# analogPWM.net
KiCad netlist of a schematic drawn in Altium Designer
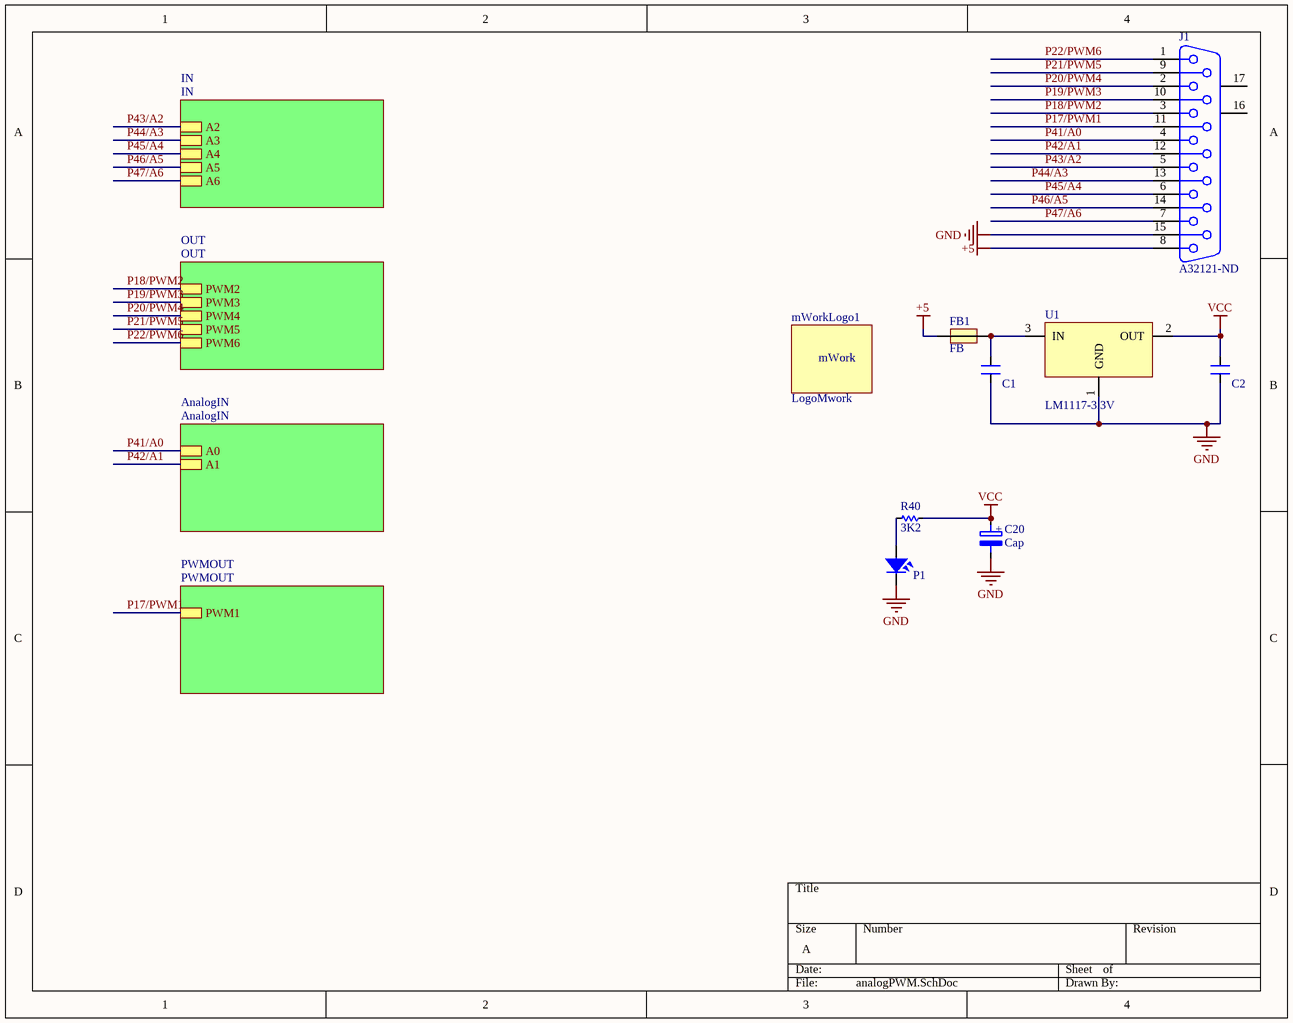
[diagram p0: analogPWM.SchDoc]

(export (version "E")
  (design (tool "Eeschema 10.0.6"))
  (components
    (comp (ref "C1") (value "100nF") (footprint "CN-SMD-0805") (libsource (lib "nhan") (part "CN")))
    (comp (ref "C2") (value "100nF") (footprint "CN-SMD-0805") (libsource (lib "nhan") (part "CN")))
    (comp (ref "C20")
      (value "Cap")
      (footprint "Cap_C")
      (description "Polarized Capacitor (Radial)")
      (libsource (lib "nhan") (part "Cap_tan"))
    )
    (comp (ref "FB1") (value "FB") (footprint "Capacitor_805") (libsource (lib "nhan") (part "FB")))
    (comp (ref "J1")
      (value "A32121-ND")
      (footprint "DB15")
      (description "Receptacle Assembly, 15 Position, Right Angle")
      (fields (field (name "PUBLISHER") "Altium Limited"))
      (libsource (lib "nhan") (part "DB15"))
    )
    (comp (ref "mWorkLogo1")
      (value "LogoMwork")
      (footprint "LogoMwork15*6")
      (libsource (lib "nhan") (part "LogoMwork"))
    )
    (comp (ref "P1")
      (value "LED")
      (footprint "LED-0805-Green")
      (libsource (lib "BanLinhKien") (part "LED SMD"))
    )
    (comp (ref "R40") (value "3K2") (footprint "RES-SMD-0805") (libsource (lib "nhan") (part "R")))
    (comp (ref "U1")
      (value "LM1117-3.3V")
      (footprint "SOT223")
      (description "800mA Low-Dropout Linear Regulator")
      (fields (field (name "CREATOR") "Nguyen Ba Bien"))
      (libsource (lib "BanLinhKien") (part "LM1117"))
    )
  )
  (nets
    (net (code "1") (name "+5") (class "Default")
      (node (ref "FB1") (pin "1") (pinfunction "1_1") (pintype "passive"))
      (node (ref "J1") (pin "8") (pinfunction "8_8") (pintype "passive"))
    )
    (net (code "2") (name "/P17{slash}PWM1") (class "Default")
      (node (ref "J1") (pin "11") (pinfunction "11_11") (pintype "passive"))
    )
    (net (code "3") (name "/P18{slash}PWM2") (class "Default")
      (node (ref "J1") (pin "3") (pinfunction "3_3") (pintype "passive"))
    )
    (net (code "4") (name "/P19{slash}PWM3") (class "Default")
      (node (ref "J1") (pin "10") (pinfunction "10_10") (pintype "passive"))
    )
    (net (code "5") (name "/P20{slash}PWM4") (class "Default")
      (node (ref "J1") (pin "2") (pinfunction "2_2") (pintype "passive"))
    )
    (net (code "6") (name "/P21{slash}PWM5") (class "Default")
      (node (ref "J1") (pin "9") (pinfunction "9_9") (pintype "passive"))
    )
    (net (code "7") (name "/P22{slash}PWM6") (class "Default")
      (node (ref "J1") (pin "1") (pinfunction "1_1") (pintype "passive"))
    )
    (net (code "8") (name "/P41{slash}A0") (class "Default")
      (node (ref "J1") (pin "4") (pinfunction "4_4") (pintype "passive"))
    )
    (net (code "9") (name "/P42{slash}A1") (class "Default")
      (node (ref "J1") (pin "12") (pinfunction "12_12") (pintype "passive"))
    )
    (net (code "10") (name "/P43{slash}A2") (class "Default")
      (node (ref "J1") (pin "5") (pinfunction "5_5") (pintype "passive"))
    )
    (net (code "11") (name "/P44{slash}A3") (class "Default")
      (node (ref "J1") (pin "13") (pinfunction "13_13") (pintype "passive"))
    )
    (net (code "12") (name "/P45{slash}A4") (class "Default")
      (node (ref "J1") (pin "6") (pinfunction "6_6") (pintype "passive"))
    )
    (net (code "13") (name "/P46{slash}A5") (class "Default")
      (node (ref "J1") (pin "14") (pinfunction "14_14") (pintype "passive"))
    )
    (net (code "14") (name "/P47{slash}A6") (class "Default")
      (node (ref "J1") (pin "7") (pinfunction "7_7") (pintype "passive"))
    )
    (net (code "15") (name "GND") (class "Default")
      (node (ref "C1") (pin "2") (pinfunction "2_2") (pintype "passive"))
      (node (ref "C2") (pin "2") (pinfunction "2_2") (pintype "passive"))
      (node (ref "C20") (pin "2") (pinfunction "2_2") (pintype "passive"))
      (node (ref "J1") (pin "15") (pinfunction "15_15") (pintype "passive"))
      (node (ref "P1") (pin "2") (pinfunction "2_2") (pintype "passive"))
      (node (ref "U1") (pin "1") (pinfunction "GND_1") (pintype "passive"))
    )
    (net (code "16") (name "Net-(P1-Pad1)") (class "Default")
      (node (ref "P1") (pin "1") (pinfunction "1_1") (pintype "passive"))
      (node (ref "R40") (pin "2") (pinfunction "2_2") (pintype "passive"))
    )
    (net (code "17") (name "Net-(U1-IN)") (class "Default")
      (node (ref "C1") (pin "1") (pinfunction "1_1") (pintype "passive"))
      (node (ref "FB1") (pin "2") (pinfunction "2_2") (pintype "passive"))
      (node (ref "U1") (pin "3") (pinfunction "IN_3") (pintype "passive"))
    )
    (net (code "18") (name "VCC") (class "Default")
      (node (ref "C2") (pin "1") (pinfunction "1_1") (pintype "passive"))
      (node (ref "C20") (pin "1") (pinfunction "1_1") (pintype "passive"))
      (node (ref "R40") (pin "1") (pinfunction "1_1") (pintype "passive"))
      (node (ref "U1") (pin "2") (pinfunction "OUT_2") (pintype "passive"))
    )
    (net (code "19") (name "unconnected-(J1-MH1-Pad16)") (class "Default")
      (node (ref "J1") (pin "16") (pinfunction "MH1_16") (pintype "passive"))
    )
    (net (code "20") (name "unconnected-(J1-MH2-Pad17)") (class "Default")
      (node (ref "J1") (pin "17") (pinfunction "MH2_17") (pintype "passive"))
    )
  )
)
